# spi_flash.net
KiCad netlist of a schematic drawn in Altium Designer
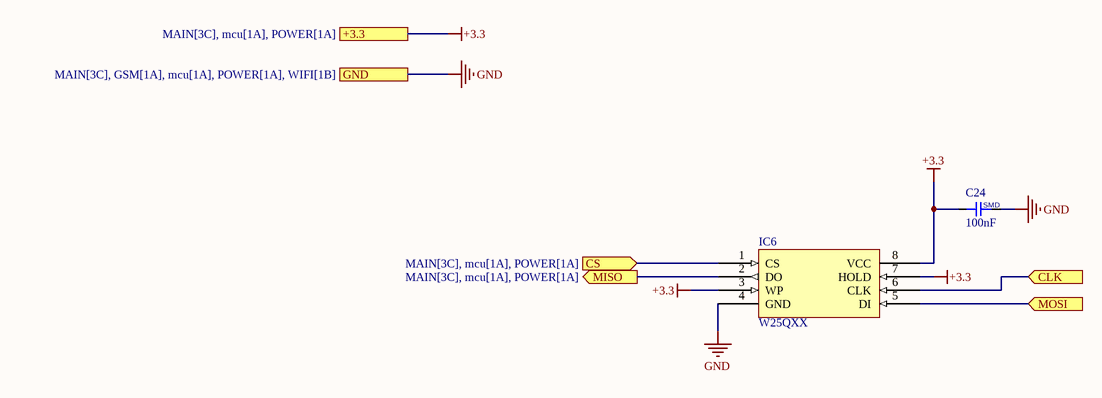
[diagram p0: spi_flash.SchDoc]

(export (version "E")
  (design (tool "Eeschema 10.0.6"))
  (components
    (comp (ref "C24")
      (value "100nF")
      (footprint "CAP-0603")
      (libsource (lib "kave-eng-pro") (part "cap_smd"))
    )
    (comp (ref "IC6")
      (value "W25QXX")
      (footprint "SOIC-8PIN-280MIL")
      (libsource (lib "kave-eng-pro") (part "w25qxx"))
    )
  )
  (nets
    (net (code "1") (name "+3.3") (class "Default")
      (node (ref "C24") (pin "1") (pintype "passive"))
      (node (ref "IC6") (pin "3") (pinfunction "WP_3") (pintype "input"))
      (node (ref "IC6") (pin "7") (pinfunction "HOLD_7") (pintype "input"))
      (node (ref "IC6") (pin "8") (pinfunction "VCC_8") (pintype "power_in"))
    )
    (net (code "2") (name "/CLK") (class "Default")
      (node (ref "IC6") (pin "6") (pinfunction "CLK_6") (pintype "input"))
    )
    (net (code "3") (name "/CS") (class "Default")
      (node (ref "IC6") (pin "1") (pinfunction "CS_1") (pintype "input"))
    )
    (net (code "4") (name "/MISO") (class "Default")
      (node (ref "IC6") (pin "2") (pinfunction "DO_2") (pintype "output"))
    )
    (net (code "5") (name "/MOSI") (class "Default")
      (node (ref "IC6") (pin "5") (pinfunction "DI_5") (pintype "input"))
    )
    (net (code "6") (name "GND") (class "Default")
      (node (ref "C24") (pin "2") (pintype "passive"))
      (node (ref "IC6") (pin "4") (pinfunction "GND_4") (pintype "power_in"))
    )
  )
)
